# 7-Segment_v2_SCH.net
KiCad netlist of a schematic drawn in Altium Designer
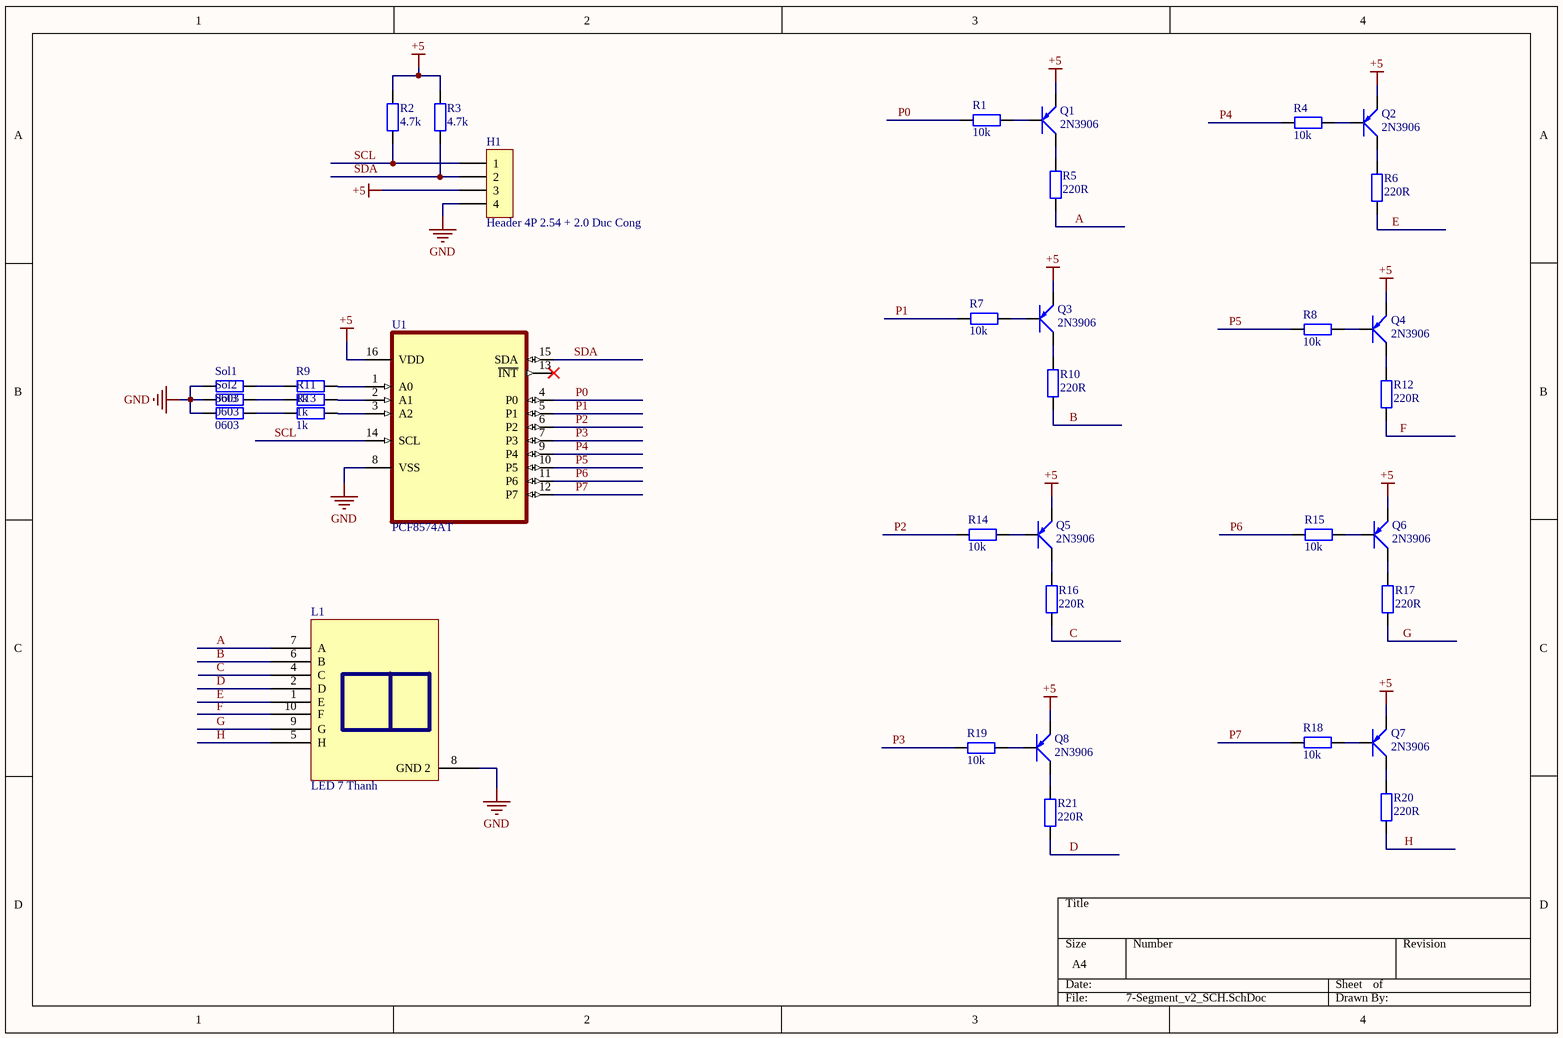
[diagram p0: 7-Segment_v2_SCH.SchDoc]

(export (version "E")
  (design (tool "Eeschema 10.0.6"))
  (components
    (comp (ref "H1")
      (value "Header 4P 2.54 + 2.0 Duc Cong")
      (footprint "Header 4P DC 2.54 + 2.0")
      (description "Cắm")
      (libsource (lib "namnt_Lib") (part "Header 4P 2.54 + 2.0 Duc Cong"))
    )
    (comp (ref "L1")
      (value "LED 7 Thanh")
      (footprint "LED 7x1 0.28")
      (description "Dán")
      (libsource (lib "namnt_Lib") (part "LED 7x1 0.28 Katot"))
    )
    (comp (ref "Q1")
      (value "2N3906")
      (footprint "SOT23")
      (description "PNP 600mW, ECB")
      (libsource (lib "namnt_Lib") (part "Trans A1015 BA SMD"))
    )
    (comp (ref "Q2")
      (value "2N3906")
      (footprint "SOT23")
      (description "PNP 600mW, ECB")
      (libsource (lib "namnt_Lib") (part "Trans A1015 BA SMD"))
    )
    (comp (ref "Q3")
      (value "2N3906")
      (footprint "SOT23")
      (description "PNP 600mW, ECB")
      (libsource (lib "namnt_Lib") (part "Trans A1015 BA SMD"))
    )
    (comp (ref "Q4")
      (value "2N3906")
      (footprint "SOT23")
      (description "PNP 600mW, ECB")
      (libsource (lib "namnt_Lib") (part "Trans A1015 BA SMD"))
    )
    (comp (ref "Q5")
      (value "2N3906")
      (footprint "SOT23")
      (description "PNP 600mW, ECB")
      (libsource (lib "namnt_Lib") (part "Trans A1015 BA SMD"))
    )
    (comp (ref "Q6")
      (value "2N3906")
      (footprint "SOT23")
      (description "PNP 600mW, ECB")
      (libsource (lib "namnt_Lib") (part "Trans A1015 BA SMD"))
    )
    (comp (ref "Q7")
      (value "2N3906")
      (footprint "SOT23")
      (description "PNP 600mW, ECB")
      (libsource (lib "namnt_Lib") (part "Trans A1015 BA SMD"))
    )
    (comp (ref "Q8")
      (value "2N3906")
      (footprint "SOT23")
      (description "PNP 600mW, ECB")
      (libsource (lib "namnt_Lib") (part "Trans A1015 BA SMD"))
    )
    (comp (ref "R1")
      (value "10k")
      (footprint "tro smd 0603")
      (description "Dán")
      (libsource (lib "namnt_Lib") (part "Tro 0603 1% 10k"))
    )
    (comp (ref "R2")
      (value "4.7k")
      (footprint "tro smd 0603")
      (description "Dán")
      (libsource (lib "namnt_Lib") (part "Tro 0603 1% 10k"))
    )
    (comp (ref "R3")
      (value "4.7k")
      (footprint "tro smd 0603")
      (description "Dán")
      (libsource (lib "namnt_Lib") (part "Tro 0603 1% 10k"))
    )
    (comp (ref "R4")
      (value "10k")
      (footprint "tro smd 0603")
      (description "Dán")
      (libsource (lib "namnt_Lib") (part "Tro 0603 1% 10k"))
    )
    (comp (ref "R5")
      (value "220R")
      (footprint "tro smd 0603")
      (description "Dán")
      (libsource (lib "namnt_Lib") (part "Tro 0603 5% 220R"))
    )
    (comp (ref "R6")
      (value "220R")
      (footprint "tro smd 0603")
      (description "Dán")
      (libsource (lib "namnt_Lib") (part "Tro 0603 5% 220R"))
    )
    (comp (ref "R7")
      (value "10k")
      (footprint "tro smd 0603")
      (description "Dán")
      (libsource (lib "namnt_Lib") (part "Tro 0603 1% 10k"))
    )
    (comp (ref "R8")
      (value "10k")
      (footprint "tro smd 0603")
      (description "Dán")
      (libsource (lib "namnt_Lib") (part "Tro 0603 1% 10k"))
    )
    (comp (ref "R9")
      (value "1k")
      (footprint "tro smd 0603")
      (description "Dán")
      (libsource (lib "namnt_Lib") (part "Tro 0603 1% 1k"))
    )
    (comp (ref "R10")
      (value "220R")
      (footprint "tro smd 0603")
      (description "Dán")
      (libsource (lib "namnt_Lib") (part "Tro 0603 5% 220R"))
    )
    (comp (ref "R11")
      (value "1k")
      (footprint "tro smd 0603")
      (description "Dán")
      (libsource (lib "namnt_Lib") (part "Tro 0603 1% 1k"))
    )
    (comp (ref "R12")
      (value "220R")
      (footprint "tro smd 0603")
      (description "Dán")
      (libsource (lib "namnt_Lib") (part "Tro 0603 5% 220R"))
    )
    (comp (ref "R13")
      (value "1k")
      (footprint "tro smd 0603")
      (description "Dán")
      (libsource (lib "namnt_Lib") (part "Tro 0603 1% 1k"))
    )
    (comp (ref "R14")
      (value "10k")
      (footprint "tro smd 0603")
      (description "Dán")
      (libsource (lib "namnt_Lib") (part "Tro 0603 1% 10k"))
    )
    (comp (ref "R15")
      (value "10k")
      (footprint "tro smd 0603")
      (description "Dán")
      (libsource (lib "namnt_Lib") (part "Tro 0603 1% 10k"))
    )
    (comp (ref "R16")
      (value "220R")
      (footprint "tro smd 0603")
      (description "Dán")
      (libsource (lib "namnt_Lib") (part "Tro 0603 5% 220R"))
    )
    (comp (ref "R17")
      (value "220R")
      (footprint "tro smd 0603")
      (description "Dán")
      (libsource (lib "namnt_Lib") (part "Tro 0603 5% 220R"))
    )
    (comp (ref "R18")
      (value "10k")
      (footprint "tro smd 0603")
      (description "Dán")
      (libsource (lib "namnt_Lib") (part "Tro 0603 1% 10k"))
    )
    (comp (ref "R19")
      (value "10k")
      (footprint "tro smd 0603")
      (description "Dán")
      (libsource (lib "namnt_Lib") (part "Tro 0603 1% 10k"))
    )
    (comp (ref "R20")
      (value "220R")
      (footprint "tro smd 0603")
      (description "Dán")
      (libsource (lib "namnt_Lib") (part "Tro 0603 5% 220R"))
    )
    (comp (ref "R21")
      (value "220R")
      (footprint "tro smd 0603")
      (description "Dán")
      (libsource (lib "namnt_Lib") (part "Tro 0603 5% 220R"))
    )
    (comp (ref "Sol1")
      (value "0603")
      (footprint "Solder 0603")
      (description "Dán")
      (libsource (lib "namnt_Lib") (part "Solder 0603"))
    )
    (comp (ref "Sol2")
      (value "0603")
      (footprint "Solder 0603")
      (description "Dán")
      (libsource (lib "namnt_Lib") (part "Solder 0603"))
    )
    (comp (ref "Sol3")
      (value "0603")
      (footprint "Solder 0603")
      (description "Dán")
      (libsource (lib "namnt_Lib") (part "Solder 0603"))
    )
    (comp (ref "U1")
      (value "PCF8574AT")
      (footprint "SOIC127P1032X265-16N")
      (description "IÂ²C Bus IC Operating temperature: -40...+85 Â°C Power supply: 2.5...6 V Package: SO-16W")
      (fields (field (name "MF") "NXP USA"))
      (libsource (lib "namnt_Lib") (part "PCF8574AT"))
    )
  )
  (nets
    (net (code "1") (name "+5") (class "Default")
      (node (ref "H1") (pin "3") (pinfunction "3_3") (pintype "passive"))
      (node (ref "Q1") (pin "2") (pinfunction "E_2") (pintype "passive"))
      (node (ref "Q2") (pin "2") (pinfunction "E_2") (pintype "passive"))
      (node (ref "Q3") (pin "2") (pinfunction "E_2") (pintype "passive"))
      (node (ref "Q4") (pin "2") (pinfunction "E_2") (pintype "passive"))
      (node (ref "Q5") (pin "2") (pinfunction "E_2") (pintype "passive"))
      (node (ref "Q6") (pin "2") (pinfunction "E_2") (pintype "passive"))
      (node (ref "Q7") (pin "2") (pinfunction "E_2") (pintype "passive"))
      (node (ref "Q8") (pin "2") (pinfunction "E_2") (pintype "passive"))
      (node (ref "R2") (pin "2") (pinfunction "2_2") (pintype "passive"))
      (node (ref "R3") (pin "2") (pinfunction "2_2") (pintype "passive"))
      (node (ref "U1") (pin "16") (pinfunction "VDD_16") (pintype "power_in"))
    )
    (net (code "2") (name "/A") (class "Default")
      (node (ref "L1") (pin "7") (pinfunction "A_7") (pintype "passive"))
      (node (ref "R5") (pin "1") (pinfunction "1_1") (pintype "passive"))
    )
    (net (code "3") (name "/B") (class "Default")
      (node (ref "L1") (pin "6") (pinfunction "B_6") (pintype "passive"))
      (node (ref "R10") (pin "1") (pinfunction "1_1") (pintype "passive"))
    )
    (net (code "4") (name "/C") (class "Default")
      (node (ref "L1") (pin "4") (pinfunction "C_4") (pintype "passive"))
      (node (ref "R16") (pin "1") (pinfunction "1_1") (pintype "passive"))
    )
    (net (code "5") (name "/D") (class "Default")
      (node (ref "L1") (pin "2") (pinfunction "D_2") (pintype "passive"))
      (node (ref "R21") (pin "1") (pinfunction "1_1") (pintype "passive"))
    )
    (net (code "6") (name "/E") (class "Default")
      (node (ref "L1") (pin "1") (pinfunction "E_1") (pintype "passive"))
      (node (ref "R6") (pin "1") (pinfunction "1_1") (pintype "passive"))
    )
    (net (code "7") (name "/F") (class "Default")
      (node (ref "L1") (pin "10") (pinfunction "F_10") (pintype "passive"))
      (node (ref "R12") (pin "1") (pinfunction "1_1") (pintype "passive"))
    )
    (net (code "8") (name "/G") (class "Default")
      (node (ref "L1") (pin "9") (pinfunction "G_9") (pintype "passive"))
      (node (ref "R17") (pin "1") (pinfunction "1_1") (pintype "passive"))
    )
    (net (code "9") (name "/H") (class "Default")
      (node (ref "L1") (pin "5") (pinfunction "H_5") (pintype "passive"))
      (node (ref "R20") (pin "1") (pinfunction "1_1") (pintype "passive"))
    )
    (net (code "10") (name "/P0") (class "Default")
      (node (ref "R1") (pin "1") (pinfunction "1_1") (pintype "passive"))
      (node (ref "U1") (pin "4") (pinfunction "P0_4") (pintype "bidirectional"))
    )
    (net (code "11") (name "/P1") (class "Default")
      (node (ref "R7") (pin "1") (pinfunction "1_1") (pintype "passive"))
      (node (ref "U1") (pin "5") (pinfunction "P1_5") (pintype "bidirectional"))
    )
    (net (code "12") (name "/P2") (class "Default")
      (node (ref "R14") (pin "1") (pinfunction "1_1") (pintype "passive"))
      (node (ref "U1") (pin "6") (pinfunction "P2_6") (pintype "bidirectional"))
    )
    (net (code "13") (name "/P3") (class "Default")
      (node (ref "R19") (pin "1") (pinfunction "1_1") (pintype "passive"))
      (node (ref "U1") (pin "7") (pinfunction "P3_7") (pintype "bidirectional"))
    )
    (net (code "14") (name "/P4") (class "Default")
      (node (ref "R4") (pin "1") (pinfunction "1_1") (pintype "passive"))
      (node (ref "U1") (pin "9") (pinfunction "P4_9") (pintype "bidirectional"))
    )
    (net (code "15") (name "/P5") (class "Default")
      (node (ref "R8") (pin "1") (pinfunction "1_1") (pintype "passive"))
      (node (ref "U1") (pin "10") (pinfunction "P5_10") (pintype "bidirectional"))
    )
    (net (code "16") (name "/P6") (class "Default")
      (node (ref "R15") (pin "1") (pinfunction "1_1") (pintype "passive"))
      (node (ref "U1") (pin "11") (pinfunction "P6_11") (pintype "bidirectional"))
    )
    (net (code "17") (name "/P7") (class "Default")
      (node (ref "R18") (pin "1") (pinfunction "1_1") (pintype "passive"))
      (node (ref "U1") (pin "12") (pinfunction "P7_12") (pintype "bidirectional"))
    )
    (net (code "18") (name "/SCL") (class "Default")
      (node (ref "H1") (pin "1") (pinfunction "1_1") (pintype "passive"))
      (node (ref "R2") (pin "1") (pinfunction "1_1") (pintype "passive"))
      (node (ref "U1") (pin "14") (pinfunction "SCL_14") (pintype "input"))
    )
    (net (code "19") (name "/SDA") (class "Default")
      (node (ref "H1") (pin "2") (pinfunction "2_2") (pintype "passive"))
      (node (ref "R3") (pin "1") (pinfunction "1_1") (pintype "passive"))
      (node (ref "U1") (pin "15") (pinfunction "SDA_15") (pintype "bidirectional"))
    )
    (net (code "20") (name "GND") (class "Default")
      (node (ref "H1") (pin "4") (pinfunction "4_4") (pintype "passive"))
      (node (ref "L1") (pin "8") (pinfunction "GND_2_8") (pintype "passive"))
      (node (ref "Sol1") (pin "1") (pinfunction "1_1") (pintype "passive"))
      (node (ref "Sol2") (pin "1") (pinfunction "1_1") (pintype "passive"))
      (node (ref "Sol3") (pin "1") (pinfunction "1_1") (pintype "passive"))
      (node (ref "U1") (pin "8") (pinfunction "VSS_8") (pintype "passive"))
    )
    (net (code "21") (name "Net-(Q1-B)") (class "Default")
      (node (ref "Q1") (pin "1") (pinfunction "B_1") (pintype "passive"))
      (node (ref "R1") (pin "2") (pinfunction "2_2") (pintype "passive"))
    )
    (net (code "22") (name "Net-(Q1-C)") (class "Default")
      (node (ref "Q1") (pin "3") (pinfunction "C_3") (pintype "passive"))
      (node (ref "R5") (pin "2") (pinfunction "2_2") (pintype "passive"))
    )
    (net (code "23") (name "Net-(Q2-B)") (class "Default")
      (node (ref "Q2") (pin "1") (pinfunction "B_1") (pintype "passive"))
      (node (ref "R4") (pin "2") (pinfunction "2_2") (pintype "passive"))
    )
    (net (code "24") (name "Net-(Q2-C)") (class "Default")
      (node (ref "Q2") (pin "3") (pinfunction "C_3") (pintype "passive"))
      (node (ref "R6") (pin "2") (pinfunction "2_2") (pintype "passive"))
    )
    (net (code "25") (name "Net-(Q3-B)") (class "Default")
      (node (ref "Q3") (pin "1") (pinfunction "B_1") (pintype "passive"))
      (node (ref "R7") (pin "2") (pinfunction "2_2") (pintype "passive"))
    )
    (net (code "26") (name "Net-(Q3-C)") (class "Default")
      (node (ref "Q3") (pin "3") (pinfunction "C_3") (pintype "passive"))
      (node (ref "R10") (pin "2") (pinfunction "2_2") (pintype "passive"))
    )
    (net (code "27") (name "Net-(Q4-B)") (class "Default")
      (node (ref "Q4") (pin "1") (pinfunction "B_1") (pintype "passive"))
      (node (ref "R8") (pin "2") (pinfunction "2_2") (pintype "passive"))
    )
    (net (code "28") (name "Net-(Q4-C)") (class "Default")
      (node (ref "Q4") (pin "3") (pinfunction "C_3") (pintype "passive"))
      (node (ref "R12") (pin "2") (pinfunction "2_2") (pintype "passive"))
    )
    (net (code "29") (name "Net-(Q5-B)") (class "Default")
      (node (ref "Q5") (pin "1") (pinfunction "B_1") (pintype "passive"))
      (node (ref "R14") (pin "2") (pinfunction "2_2") (pintype "passive"))
    )
    (net (code "30") (name "Net-(Q5-C)") (class "Default")
      (node (ref "Q5") (pin "3") (pinfunction "C_3") (pintype "passive"))
      (node (ref "R16") (pin "2") (pinfunction "2_2") (pintype "passive"))
    )
    (net (code "31") (name "Net-(Q6-B)") (class "Default")
      (node (ref "Q6") (pin "1") (pinfunction "B_1") (pintype "passive"))
      (node (ref "R15") (pin "2") (pinfunction "2_2") (pintype "passive"))
    )
    (net (code "32") (name "Net-(Q6-C)") (class "Default")
      (node (ref "Q6") (pin "3") (pinfunction "C_3") (pintype "passive"))
      (node (ref "R17") (pin "2") (pinfunction "2_2") (pintype "passive"))
    )
    (net (code "33") (name "Net-(Q7-B)") (class "Default")
      (node (ref "Q7") (pin "1") (pinfunction "B_1") (pintype "passive"))
      (node (ref "R18") (pin "2") (pinfunction "2_2") (pintype "passive"))
    )
    (net (code "34") (name "Net-(Q7-C)") (class "Default")
      (node (ref "Q7") (pin "3") (pinfunction "C_3") (pintype "passive"))
      (node (ref "R20") (pin "2") (pinfunction "2_2") (pintype "passive"))
    )
    (net (code "35") (name "Net-(Q8-B)") (class "Default")
      (node (ref "Q8") (pin "1") (pinfunction "B_1") (pintype "passive"))
      (node (ref "R19") (pin "2") (pinfunction "2_2") (pintype "passive"))
    )
    (net (code "36") (name "Net-(Q8-C)") (class "Default")
      (node (ref "Q8") (pin "3") (pinfunction "C_3") (pintype "passive"))
      (node (ref "R21") (pin "2") (pinfunction "2_2") (pintype "passive"))
    )
    (net (code "37") (name "Net-(R9-Pad1)") (class "Default")
      (node (ref "R9") (pin "1") (pinfunction "1_1") (pintype "passive"))
      (node (ref "Sol1") (pin "2") (pinfunction "2_2") (pintype "passive"))
    )
    (net (code "38") (name "Net-(R11-Pad1)") (class "Default")
      (node (ref "R11") (pin "1") (pinfunction "1_1") (pintype "passive"))
      (node (ref "Sol2") (pin "2") (pinfunction "2_2") (pintype "passive"))
    )
    (net (code "39") (name "Net-(R13-Pad1)") (class "Default")
      (node (ref "R13") (pin "1") (pinfunction "1_1") (pintype "passive"))
      (node (ref "Sol3") (pin "2") (pinfunction "2_2") (pintype "passive"))
    )
    (net (code "40") (name "Net-(U1-A0)") (class "Default")
      (node (ref "R9") (pin "2") (pinfunction "2_2") (pintype "passive"))
      (node (ref "U1") (pin "1") (pinfunction "A0_1") (pintype "input"))
    )
    (net (code "41") (name "Net-(U1-A1)") (class "Default")
      (node (ref "R11") (pin "2") (pinfunction "2_2") (pintype "passive"))
      (node (ref "U1") (pin "2") (pinfunction "A1_2") (pintype "input"))
    )
    (net (code "42") (name "Net-(U1-A2)") (class "Default")
      (node (ref "R13") (pin "2") (pinfunction "2_2") (pintype "passive"))
      (node (ref "U1") (pin "3") (pinfunction "A2_3") (pintype "input"))
    )
    (net (code "43") (name "unconnected-(U1-~{INT}-Pad13)") (class "Default")
      (node (ref "U1") (pin "13") (pinfunction "~{INT}_13") (pintype "output+no_connect"))
    )
  )
)
